# LED_TEST.net
KiCad netlist of a schematic drawn in EAGLE
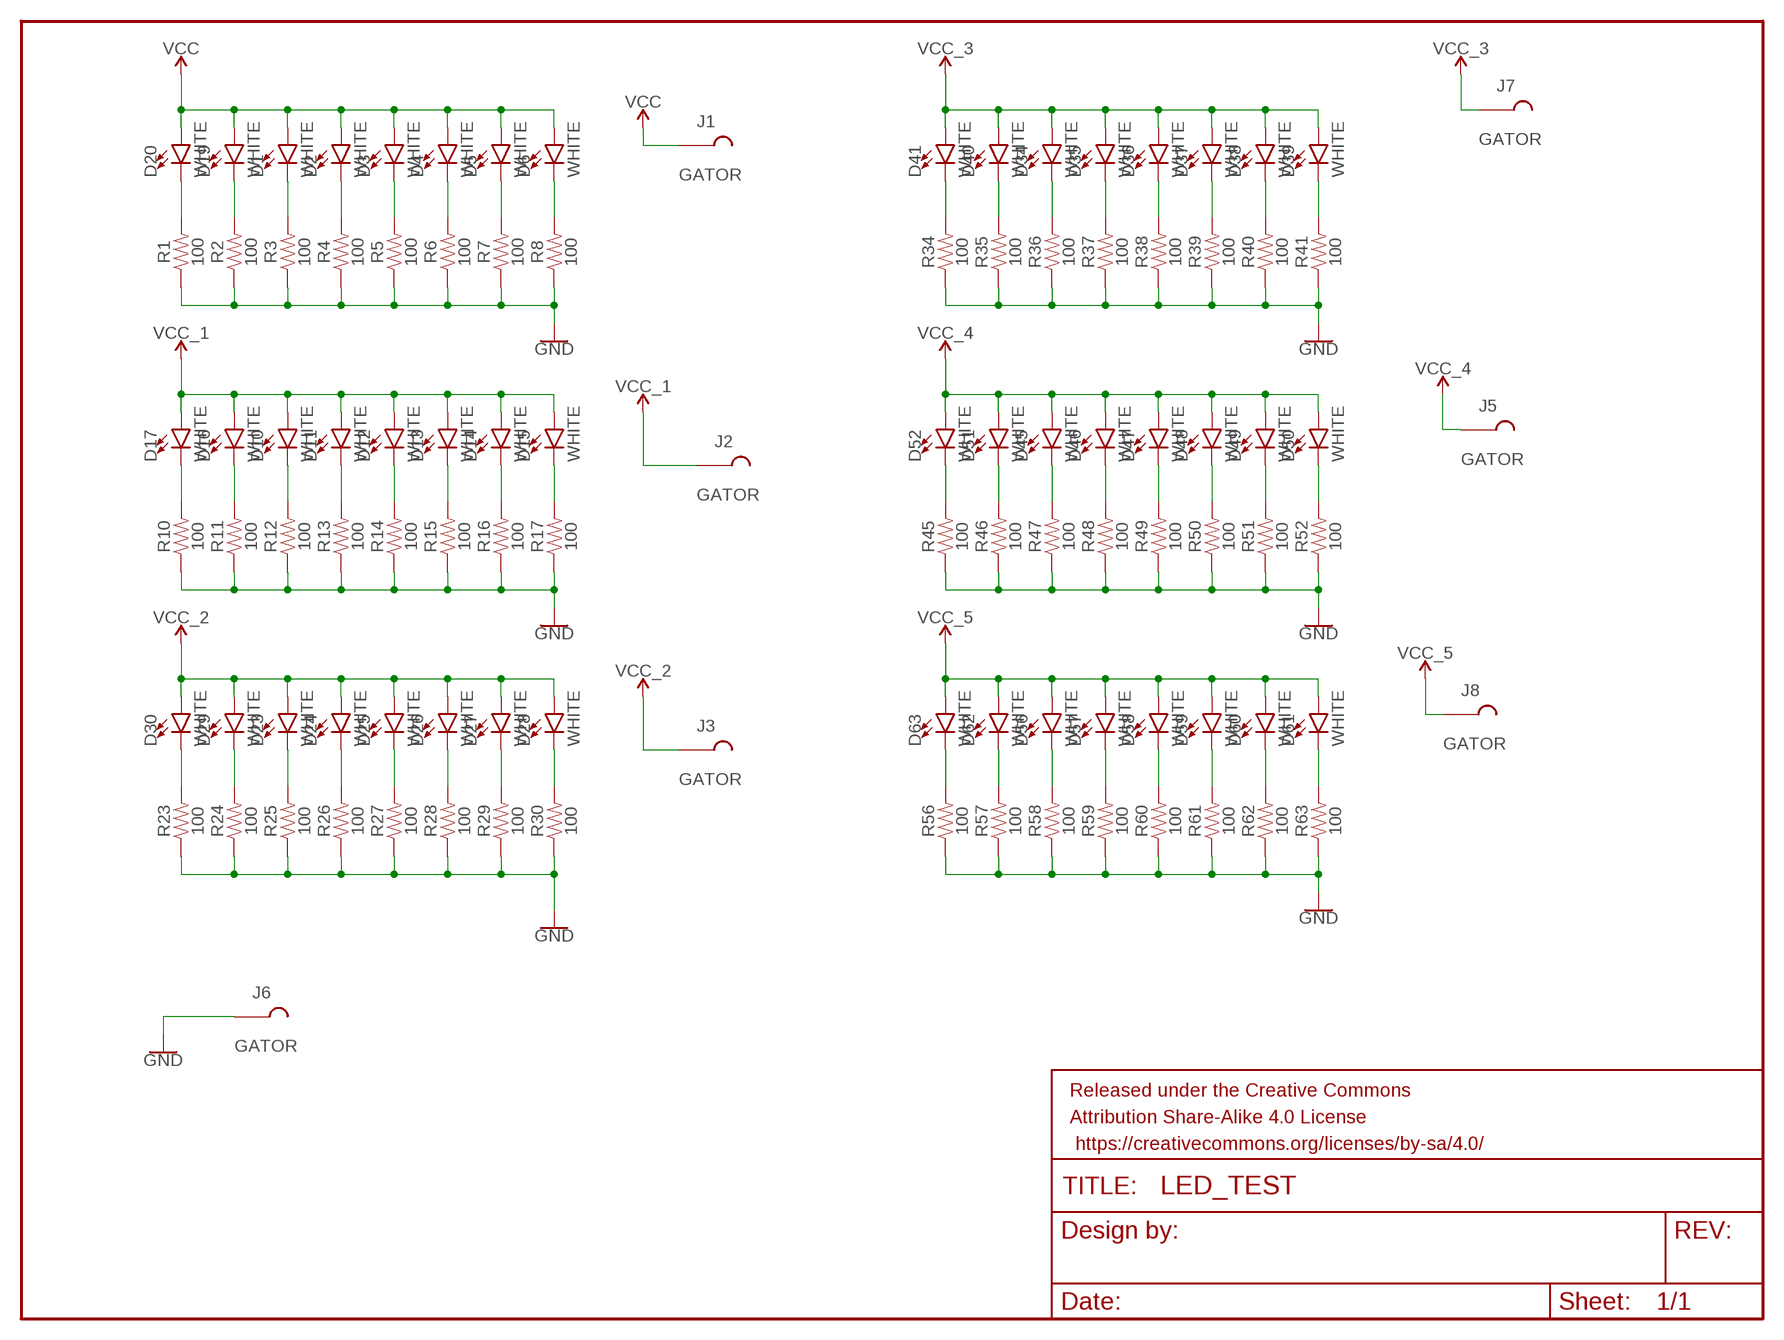
[diagram p0: schematic, sheet 1]

(export (version "E")
  (design (tool "Eeschema 10.0.6"))
  (components
    (comp (ref "D1")
      (value "WHITE")
      (footprint "eagle-import:LED-1206")
      (libsource (lib "eagle-import") (part "LED-WHITE1206"))
    )
    (comp (ref "D2")
      (value "WHITE")
      (footprint "eagle-import:LED-1206")
      (libsource (lib "eagle-import") (part "LED-WHITE1206"))
    )
    (comp (ref "D3")
      (value "WHITE")
      (footprint "eagle-import:LED-1206")
      (libsource (lib "eagle-import") (part "LED-WHITE1206"))
    )
    (comp (ref "D4")
      (value "WHITE")
      (footprint "eagle-import:LED-1206")
      (libsource (lib "eagle-import") (part "LED-WHITE1206"))
    )
    (comp (ref "D5")
      (value "WHITE")
      (footprint "eagle-import:LED-1206")
      (libsource (lib "eagle-import") (part "LED-WHITE1206"))
    )
    (comp (ref "D6")
      (value "WHITE")
      (footprint "eagle-import:LED-1206")
      (libsource (lib "eagle-import") (part "LED-WHITE1206"))
    )
    (comp (ref "D10")
      (value "WHITE")
      (footprint "eagle-import:LED-1206")
      (libsource (lib "eagle-import") (part "LED-WHITE1206"))
    )
    (comp (ref "D11")
      (value "WHITE")
      (footprint "eagle-import:LED-1206")
      (libsource (lib "eagle-import") (part "LED-WHITE1206"))
    )
    (comp (ref "D12")
      (value "WHITE")
      (footprint "eagle-import:LED-1206")
      (libsource (lib "eagle-import") (part "LED-WHITE1206"))
    )
    (comp (ref "D13")
      (value "WHITE")
      (footprint "eagle-import:LED-1206")
      (libsource (lib "eagle-import") (part "LED-WHITE1206"))
    )
    (comp (ref "D14")
      (value "WHITE")
      (footprint "eagle-import:LED-1206")
      (libsource (lib "eagle-import") (part "LED-WHITE1206"))
    )
    (comp (ref "D15")
      (value "WHITE")
      (footprint "eagle-import:LED-1206")
      (libsource (lib "eagle-import") (part "LED-WHITE1206"))
    )
    (comp (ref "D16")
      (value "WHITE")
      (footprint "eagle-import:LED-1206")
      (libsource (lib "eagle-import") (part "LED-WHITE1206"))
    )
    (comp (ref "D17")
      (value "WHITE")
      (footprint "eagle-import:LED-1206")
      (libsource (lib "eagle-import") (part "LED-WHITE1206"))
    )
    (comp (ref "D19")
      (value "WHITE")
      (footprint "eagle-import:LED-1206")
      (libsource (lib "eagle-import") (part "LED-WHITE1206"))
    )
    (comp (ref "D20")
      (value "WHITE")
      (footprint "eagle-import:LED-1206")
      (libsource (lib "eagle-import") (part "LED-WHITE1206"))
    )
    (comp (ref "D23")
      (value "WHITE")
      (footprint "eagle-import:LED-1206")
      (libsource (lib "eagle-import") (part "LED-WHITE1206"))
    )
    (comp (ref "D24")
      (value "WHITE")
      (footprint "eagle-import:LED-1206")
      (libsource (lib "eagle-import") (part "LED-WHITE1206"))
    )
    (comp (ref "D25")
      (value "WHITE")
      (footprint "eagle-import:LED-1206")
      (libsource (lib "eagle-import") (part "LED-WHITE1206"))
    )
    (comp (ref "D26")
      (value "WHITE")
      (footprint "eagle-import:LED-1206")
      (libsource (lib "eagle-import") (part "LED-WHITE1206"))
    )
    (comp (ref "D27")
      (value "WHITE")
      (footprint "eagle-import:LED-1206")
      (libsource (lib "eagle-import") (part "LED-WHITE1206"))
    )
    (comp (ref "D28")
      (value "WHITE")
      (footprint "eagle-import:LED-1206")
      (libsource (lib "eagle-import") (part "LED-WHITE1206"))
    )
    (comp (ref "D29")
      (value "WHITE")
      (footprint "eagle-import:LED-1206")
      (libsource (lib "eagle-import") (part "LED-WHITE1206"))
    )
    (comp (ref "D30")
      (value "WHITE")
      (footprint "eagle-import:LED-1206")
      (libsource (lib "eagle-import") (part "LED-WHITE1206"))
    )
    (comp (ref "D34")
      (value "WHITE")
      (footprint "eagle-import:LED-1206")
      (libsource (lib "eagle-import") (part "LED-WHITE1206"))
    )
    (comp (ref "D35")
      (value "WHITE")
      (footprint "eagle-import:LED-1206")
      (libsource (lib "eagle-import") (part "LED-WHITE1206"))
    )
    (comp (ref "D36")
      (value "WHITE")
      (footprint "eagle-import:LED-1206")
      (libsource (lib "eagle-import") (part "LED-WHITE1206"))
    )
    (comp (ref "D37")
      (value "WHITE")
      (footprint "eagle-import:LED-1206")
      (libsource (lib "eagle-import") (part "LED-WHITE1206"))
    )
    (comp (ref "D38")
      (value "WHITE")
      (footprint "eagle-import:LED-1206")
      (libsource (lib "eagle-import") (part "LED-WHITE1206"))
    )
    (comp (ref "D39")
      (value "WHITE")
      (footprint "eagle-import:LED-1206")
      (libsource (lib "eagle-import") (part "LED-WHITE1206"))
    )
    (comp (ref "D40")
      (value "WHITE")
      (footprint "eagle-import:LED-1206")
      (libsource (lib "eagle-import") (part "LED-WHITE1206"))
    )
    (comp (ref "D41")
      (value "WHITE")
      (footprint "eagle-import:LED-1206")
      (libsource (lib "eagle-import") (part "LED-WHITE1206"))
    )
    (comp (ref "D45")
      (value "WHITE")
      (footprint "eagle-import:LED-1206")
      (libsource (lib "eagle-import") (part "LED-WHITE1206"))
    )
    (comp (ref "D46")
      (value "WHITE")
      (footprint "eagle-import:LED-1206")
      (libsource (lib "eagle-import") (part "LED-WHITE1206"))
    )
    (comp (ref "D47")
      (value "WHITE")
      (footprint "eagle-import:LED-1206")
      (libsource (lib "eagle-import") (part "LED-WHITE1206"))
    )
    (comp (ref "D48")
      (value "WHITE")
      (footprint "eagle-import:LED-1206")
      (libsource (lib "eagle-import") (part "LED-WHITE1206"))
    )
    (comp (ref "D49")
      (value "WHITE")
      (footprint "eagle-import:LED-1206")
      (libsource (lib "eagle-import") (part "LED-WHITE1206"))
    )
    (comp (ref "D50")
      (value "WHITE")
      (footprint "eagle-import:LED-1206")
      (libsource (lib "eagle-import") (part "LED-WHITE1206"))
    )
    (comp (ref "D51")
      (value "WHITE")
      (footprint "eagle-import:LED-1206")
      (libsource (lib "eagle-import") (part "LED-WHITE1206"))
    )
    (comp (ref "D52")
      (value "WHITE")
      (footprint "eagle-import:LED-1206")
      (libsource (lib "eagle-import") (part "LED-WHITE1206"))
    )
    (comp (ref "D56")
      (value "WHITE")
      (footprint "eagle-import:LED-1206")
      (libsource (lib "eagle-import") (part "LED-WHITE1206"))
    )
    (comp (ref "D57")
      (value "WHITE")
      (footprint "eagle-import:LED-1206")
      (libsource (lib "eagle-import") (part "LED-WHITE1206"))
    )
    (comp (ref "D58")
      (value "WHITE")
      (footprint "eagle-import:LED-1206")
      (libsource (lib "eagle-import") (part "LED-WHITE1206"))
    )
    (comp (ref "D59")
      (value "WHITE")
      (footprint "eagle-import:LED-1206")
      (libsource (lib "eagle-import") (part "LED-WHITE1206"))
    )
    (comp (ref "D60")
      (value "WHITE")
      (footprint "eagle-import:LED-1206")
      (libsource (lib "eagle-import") (part "LED-WHITE1206"))
    )
    (comp (ref "D61")
      (value "WHITE")
      (footprint "eagle-import:LED-1206")
      (libsource (lib "eagle-import") (part "LED-WHITE1206"))
    )
    (comp (ref "D62")
      (value "WHITE")
      (footprint "eagle-import:LED-1206")
      (libsource (lib "eagle-import") (part "LED-WHITE1206"))
    )
    (comp (ref "D63")
      (value "WHITE")
      (footprint "eagle-import:LED-1206")
      (libsource (lib "eagle-import") (part "LED-WHITE1206"))
    )
    (comp (ref "FRAME1")
      (value "FRAME-LETTER")
      (footprint "eagle-import:CREATIVE_COMMONS")
      (libsource (lib "eagle-import") (part "FRAME-LETTER"))
    )
    (comp (ref "J1")
      (value "GATOR")
      (footprint "eagle-import:GATOR")
      (libsource (lib "eagle-import") (part "GATOR"))
    )
    (comp (ref "J2")
      (value "GATOR")
      (footprint "eagle-import:GATOR")
      (libsource (lib "eagle-import") (part "GATOR"))
    )
    (comp (ref "J3")
      (value "GATOR")
      (footprint "eagle-import:GATOR")
      (libsource (lib "eagle-import") (part "GATOR"))
    )
    (comp (ref "J5")
      (value "GATOR")
      (footprint "eagle-import:GATOR")
      (libsource (lib "eagle-import") (part "GATOR"))
    )
    (comp (ref "J6")
      (value "GATOR")
      (footprint "eagle-import:GATOR")
      (libsource (lib "eagle-import") (part "GATOR"))
    )
    (comp (ref "J7")
      (value "GATOR")
      (footprint "eagle-import:GATOR")
      (libsource (lib "eagle-import") (part "GATOR"))
    )
    (comp (ref "J8")
      (value "GATOR")
      (footprint "eagle-import:GATOR")
      (libsource (lib "eagle-import") (part "GATOR"))
    )
    (comp (ref "R1")
      (value "100")
      (footprint "eagle-import:0603")
      (libsource (lib "eagle-import") (part "100OHM-0603-1/4W-5%"))
    )
    (comp (ref "R2")
      (value "100")
      (footprint "eagle-import:0603")
      (libsource (lib "eagle-import") (part "100OHM-0603-1/4W-5%"))
    )
    (comp (ref "R3")
      (value "100")
      (footprint "eagle-import:0603")
      (libsource (lib "eagle-import") (part "100OHM-0603-1/4W-5%"))
    )
    (comp (ref "R4")
      (value "100")
      (footprint "eagle-import:0603")
      (libsource (lib "eagle-import") (part "100OHM-0603-1/4W-5%"))
    )
    (comp (ref "R5")
      (value "100")
      (footprint "eagle-import:0603")
      (libsource (lib "eagle-import") (part "100OHM-0603-1/4W-5%"))
    )
    (comp (ref "R6")
      (value "100")
      (footprint "eagle-import:0603")
      (libsource (lib "eagle-import") (part "100OHM-0603-1/4W-5%"))
    )
    (comp (ref "R7")
      (value "100")
      (footprint "eagle-import:0603")
      (libsource (lib "eagle-import") (part "100OHM-0603-1/4W-5%"))
    )
    (comp (ref "R8")
      (value "100")
      (footprint "eagle-import:0603")
      (libsource (lib "eagle-import") (part "100OHM-0603-1/4W-5%"))
    )
    (comp (ref "R10")
      (value "100")
      (footprint "eagle-import:0603")
      (libsource (lib "eagle-import") (part "100OHM-0603-1/4W-5%"))
    )
    (comp (ref "R11")
      (value "100")
      (footprint "eagle-import:0603")
      (libsource (lib "eagle-import") (part "100OHM-0603-1/4W-5%"))
    )
    (comp (ref "R12")
      (value "100")
      (footprint "eagle-import:0603")
      (libsource (lib "eagle-import") (part "100OHM-0603-1/4W-5%"))
    )
    (comp (ref "R13")
      (value "100")
      (footprint "eagle-import:0603")
      (libsource (lib "eagle-import") (part "100OHM-0603-1/4W-5%"))
    )
    (comp (ref "R14")
      (value "100")
      (footprint "eagle-import:0603")
      (libsource (lib "eagle-import") (part "100OHM-0603-1/4W-5%"))
    )
    (comp (ref "R15")
      (value "100")
      (footprint "eagle-import:0603")
      (libsource (lib "eagle-import") (part "100OHM-0603-1/4W-5%"))
    )
    (comp (ref "R16")
      (value "100")
      (footprint "eagle-import:0603")
      (libsource (lib "eagle-import") (part "100OHM-0603-1/4W-5%"))
    )
    (comp (ref "R17")
      (value "100")
      (footprint "eagle-import:0603")
      (libsource (lib "eagle-import") (part "100OHM-0603-1/4W-5%"))
    )
    (comp (ref "R23")
      (value "100")
      (footprint "eagle-import:0603")
      (libsource (lib "eagle-import") (part "100OHM-0603-1/4W-5%"))
    )
    (comp (ref "R24")
      (value "100")
      (footprint "eagle-import:0603")
      (libsource (lib "eagle-import") (part "100OHM-0603-1/4W-5%"))
    )
    (comp (ref "R25")
      (value "100")
      (footprint "eagle-import:0603")
      (libsource (lib "eagle-import") (part "100OHM-0603-1/4W-5%"))
    )
    (comp (ref "R26")
      (value "100")
      (footprint "eagle-import:0603")
      (libsource (lib "eagle-import") (part "100OHM-0603-1/4W-5%"))
    )
    (comp (ref "R27")
      (value "100")
      (footprint "eagle-import:0603")
      (libsource (lib "eagle-import") (part "100OHM-0603-1/4W-5%"))
    )
    (comp (ref "R28")
      (value "100")
      (footprint "eagle-import:0603")
      (libsource (lib "eagle-import") (part "100OHM-0603-1/4W-5%"))
    )
    (comp (ref "R29")
      (value "100")
      (footprint "eagle-import:0603")
      (libsource (lib "eagle-import") (part "100OHM-0603-1/4W-5%"))
    )
    (comp (ref "R30")
      (value "100")
      (footprint "eagle-import:0603")
      (libsource (lib "eagle-import") (part "100OHM-0603-1/4W-5%"))
    )
    (comp (ref "R34")
      (value "100")
      (footprint "eagle-import:0603")
      (libsource (lib "eagle-import") (part "100OHM-0603-1/4W-5%"))
    )
    (comp (ref "R35")
      (value "100")
      (footprint "eagle-import:0603")
      (libsource (lib "eagle-import") (part "100OHM-0603-1/4W-5%"))
    )
    (comp (ref "R36")
      (value "100")
      (footprint "eagle-import:0603")
      (libsource (lib "eagle-import") (part "100OHM-0603-1/4W-5%"))
    )
    (comp (ref "R37")
      (value "100")
      (footprint "eagle-import:0603")
      (libsource (lib "eagle-import") (part "100OHM-0603-1/4W-5%"))
    )
    (comp (ref "R38")
      (value "100")
      (footprint "eagle-import:0603")
      (libsource (lib "eagle-import") (part "100OHM-0603-1/4W-5%"))
    )
    (comp (ref "R39")
      (value "100")
      (footprint "eagle-import:0603")
      (libsource (lib "eagle-import") (part "100OHM-0603-1/4W-5%"))
    )
    (comp (ref "R40")
      (value "100")
      (footprint "eagle-import:0603")
      (libsource (lib "eagle-import") (part "100OHM-0603-1/4W-5%"))
    )
    (comp (ref "R41")
      (value "100")
      (footprint "eagle-import:0603")
      (libsource (lib "eagle-import") (part "100OHM-0603-1/4W-5%"))
    )
    (comp (ref "R45")
      (value "100")
      (footprint "eagle-import:0603")
      (libsource (lib "eagle-import") (part "100OHM-0603-1/4W-5%"))
    )
    (comp (ref "R46")
      (value "100")
      (footprint "eagle-import:0603")
      (libsource (lib "eagle-import") (part "100OHM-0603-1/4W-5%"))
    )
    (comp (ref "R47")
      (value "100")
      (footprint "eagle-import:0603")
      (libsource (lib "eagle-import") (part "100OHM-0603-1/4W-5%"))
    )
    (comp (ref "R48")
      (value "100")
      (footprint "eagle-import:0603")
      (libsource (lib "eagle-import") (part "100OHM-0603-1/4W-5%"))
    )
    (comp (ref "R49")
      (value "100")
      (footprint "eagle-import:0603")
      (libsource (lib "eagle-import") (part "100OHM-0603-1/4W-5%"))
    )
    (comp (ref "R50")
      (value "100")
      (footprint "eagle-import:0603")
      (libsource (lib "eagle-import") (part "100OHM-0603-1/4W-5%"))
    )
    (comp (ref "R51")
      (value "100")
      (footprint "eagle-import:0603")
      (libsource (lib "eagle-import") (part "100OHM-0603-1/4W-5%"))
    )
    (comp (ref "R52")
      (value "100")
      (footprint "eagle-import:0603")
      (libsource (lib "eagle-import") (part "100OHM-0603-1/4W-5%"))
    )
    (comp (ref "R56")
      (value "100")
      (footprint "eagle-import:0603")
      (libsource (lib "eagle-import") (part "100OHM-0603-1/4W-5%"))
    )
    (comp (ref "R57")
      (value "100")
      (footprint "eagle-import:0603")
      (libsource (lib "eagle-import") (part "100OHM-0603-1/4W-5%"))
    )
    (comp (ref "R58")
      (value "100")
      (footprint "eagle-import:0603")
      (libsource (lib "eagle-import") (part "100OHM-0603-1/4W-5%"))
    )
    (comp (ref "R59")
      (value "100")
      (footprint "eagle-import:0603")
      (libsource (lib "eagle-import") (part "100OHM-0603-1/4W-5%"))
    )
    (comp (ref "R60")
      (value "100")
      (footprint "eagle-import:0603")
      (libsource (lib "eagle-import") (part "100OHM-0603-1/4W-5%"))
    )
    (comp (ref "R61")
      (value "100")
      (footprint "eagle-import:0603")
      (libsource (lib "eagle-import") (part "100OHM-0603-1/4W-5%"))
    )
    (comp (ref "R62")
      (value "100")
      (footprint "eagle-import:0603")
      (libsource (lib "eagle-import") (part "100OHM-0603-1/4W-5%"))
    )
    (comp (ref "R63")
      (value "100")
      (footprint "eagle-import:0603")
      (libsource (lib "eagle-import") (part "100OHM-0603-1/4W-5%"))
    )
  )
  (nets
    (net (code "1") (name "GND") (class "Default")
      (node (ref "J6") (pin "P$1") (pinfunction "P$1_P$1") (pintype "bidirectional"))
      (node (ref "J6") (pin "P$2") (pinfunction "P$1_P$2") (pintype "bidirectional"))
      (node (ref "R1") (pin "1") (pinfunction "1_1") (pintype "passive"))
      (node (ref "R10") (pin "1") (pinfunction "1_1") (pintype "passive"))
      (node (ref "R11") (pin "1") (pinfunction "1_1") (pintype "passive"))
      (node (ref "R12") (pin "1") (pinfunction "1_1") (pintype "passive"))
      (node (ref "R13") (pin "1") (pinfunction "1_1") (pintype "passive"))
      (node (ref "R14") (pin "1") (pinfunction "1_1") (pintype "passive"))
      (node (ref "R15") (pin "1") (pinfunction "1_1") (pintype "passive"))
      (node (ref "R16") (pin "1") (pinfunction "1_1") (pintype "passive"))
      (node (ref "R17") (pin "1") (pinfunction "1_1") (pintype "passive"))
      (node (ref "R2") (pin "1") (pinfunction "1_1") (pintype "passive"))
      (node (ref "R23") (pin "1") (pinfunction "1_1") (pintype "passive"))
      (node (ref "R24") (pin "1") (pinfunction "1_1") (pintype "passive"))
      (node (ref "R25") (pin "1") (pinfunction "1_1") (pintype "passive"))
      (node (ref "R26") (pin "1") (pinfunction "1_1") (pintype "passive"))
      (node (ref "R27") (pin "1") (pinfunction "1_1") (pintype "passive"))
      (node (ref "R28") (pin "1") (pinfunction "1_1") (pintype "passive"))
      (node (ref "R29") (pin "1") (pinfunction "1_1") (pintype "passive"))
      (node (ref "R3") (pin "1") (pinfunction "1_1") (pintype "passive"))
      (node (ref "R30") (pin "1") (pinfunction "1_1") (pintype "passive"))
      (node (ref "R34") (pin "1") (pinfunction "1_1") (pintype "passive"))
      (node (ref "R35") (pin "1") (pinfunction "1_1") (pintype "passive"))
      (node (ref "R36") (pin "1") (pinfunction "1_1") (pintype "passive"))
      (node (ref "R37") (pin "1") (pinfunction "1_1") (pintype "passive"))
      (node (ref "R38") (pin "1") (pinfunction "1_1") (pintype "passive"))
      (node (ref "R39") (pin "1") (pinfunction "1_1") (pintype "passive"))
      (node (ref "R4") (pin "1") (pinfunction "1_1") (pintype "passive"))
      (node (ref "R40") (pin "1") (pinfunction "1_1") (pintype "passive"))
      (node (ref "R41") (pin "1") (pinfunction "1_1") (pintype "passive"))
      (node (ref "R45") (pin "1") (pinfunction "1_1") (pintype "passive"))
      (node (ref "R46") (pin "1") (pinfunction "1_1") (pintype "passive"))
      (node (ref "R47") (pin "1") (pinfunction "1_1") (pintype "passive"))
      (node (ref "R48") (pin "1") (pinfunction "1_1") (pintype "passive"))
      (node (ref "R49") (pin "1") (pinfunction "1_1") (pintype "passive"))
      (node (ref "R5") (pin "1") (pinfunction "1_1") (pintype "passive"))
      (node (ref "R50") (pin "1") (pinfunction "1_1") (pintype "passive"))
      (node (ref "R51") (pin "1") (pinfunction "1_1") (pintype "passive"))
      (node (ref "R52") (pin "1") (pinfunction "1_1") (pintype "passive"))
      (node (ref "R56") (pin "1") (pinfunction "1_1") (pintype "passive"))
      (node (ref "R57") (pin "1") (pinfunction "1_1") (pintype "passive"))
      (node (ref "R58") (pin "1") (pinfunction "1_1") (pintype "passive"))
      (node (ref "R59") (pin "1") (pinfunction "1_1") (pintype "passive"))
      (node (ref "R6") (pin "1") (pinfunction "1_1") (pintype "passive"))
      (node (ref "R60") (pin "1") (pinfunction "1_1") (pintype "passive"))
      (node (ref "R61") (pin "1") (pinfunction "1_1") (pintype "passive"))
      (node (ref "R62") (pin "1") (pinfunction "1_1") (pintype "passive"))
      (node (ref "R63") (pin "1") (pinfunction "1_1") (pintype "passive"))
      (node (ref "R7") (pin "1") (pinfunction "1_1") (pintype "passive"))
      (node (ref "R8") (pin "1") (pinfunction "1_1") (pintype "passive"))
    )
    (net (code "2") (name "Net-(D1-PadC)") (class "Default")
      (node (ref "D1") (pin "C") (pinfunction "C_C") (pintype "passive"))
      (node (ref "R3") (pin "2") (pinfunction "2_2") (pintype "passive"))
    )
    (net (code "3") (name "Net-(D2-PadC)") (class "Default")
      (node (ref "D2") (pin "C") (pinfunction "C_C") (pintype "passive"))
      (node (ref "R4") (pin "2") (pinfunction "2_2") (pintype "passive"))
    )
    (net (code "4") (name "Net-(D3-PadC)") (class "Default")
      (node (ref "D3") (pin "C") (pinfunction "C_C") (pintype "passive"))
      (node (ref "R5") (pin "2") (pinfunction "2_2") (pintype "passive"))
    )
    (net (code "5") (name "Net-(D4-PadC)") (class "Default")
      (node (ref "D4") (pin "C") (pinfunction "C_C") (pintype "passive"))
      (node (ref "R6") (pin "2") (pinfunction "2_2") (pintype "passive"))
    )
    (net (code "6") (name "Net-(D5-PadC)") (class "Default")
      (node (ref "D5") (pin "C") (pinfunction "C_C") (pintype "passive"))
      (node (ref "R7") (pin "2") (pinfunction "2_2") (pintype "passive"))
    )
    (net (code "7") (name "Net-(D6-PadC)") (class "Default")
      (node (ref "D6") (pin "C") (pinfunction "C_C") (pintype "passive"))
      (node (ref "R8") (pin "2") (pinfunction "2_2") (pintype "passive"))
    )
    (net (code "8") (name "Net-(D10-PadC)") (class "Default")
      (node (ref "D10") (pin "C") (pinfunction "C_C") (pintype "passive"))
      (node (ref "R12") (pin "2") (pinfunction "2_2") (pintype "passive"))
    )
    (net (code "9") (name "Net-(D11-PadC)") (class "Default")
      (node (ref "D11") (pin "C") (pinfunction "C_C") (pintype "passive"))
      (node (ref "R13") (pin "2") (pinfunction "2_2") (pintype "passive"))
    )
    (net (code "10") (name "Net-(D12-PadC)") (class "Default")
      (node (ref "D12") (pin "C") (pinfunction "C_C") (pintype "passive"))
      (node (ref "R14") (pin "2") (pinfunction "2_2") (pintype "passive"))
    )
    (net (code "11") (name "Net-(D13-PadC)") (class "Default")
      (node (ref "D13") (pin "C") (pinfunction "C_C") (pintype "passive"))
      (node (ref "R15") (pin "2") (pinfunction "2_2") (pintype "passive"))
    )
    (net (code "12") (name "Net-(D14-PadC)") (class "Default")
      (node (ref "D14") (pin "C") (pinfunction "C_C") (pintype "passive"))
      (node (ref "R16") (pin "2") (pinfunction "2_2") (pintype "passive"))
    )
    (net (code "13") (name "Net-(D15-PadC)") (class "Default")
      (node (ref "D15") (pin "C") (pinfunction "C_C") (pintype "passive"))
      (node (ref "R17") (pin "2") (pinfunction "2_2") (pintype "passive"))
    )
    (net (code "14") (name "Net-(D16-PadC)") (class "Default")
      (node (ref "D16") (pin "C") (pinfunction "C_C") (pintype "passive"))
      (node (ref "R11") (pin "2") (pinfunction "2_2") (pintype "passive"))
    )
    (net (code "15") (name "Net-(D17-PadC)") (class "Default")
      (node (ref "D17") (pin "C") (pinfunction "C_C") (pintype "passive"))
      (node (ref "R10") (pin "2") (pinfunction "2_2") (pintype "passive"))
    )
    (net (code "16") (name "Net-(D19-PadC)") (class "Default")
      (node (ref "D19") (pin "C") (pinfunction "C_C") (pintype "passive"))
      (node (ref "R2") (pin "2") (pinfunction "2_2") (pintype "passive"))
    )
    (net (code "17") (name "Net-(D20-PadC)") (class "Default")
      (node (ref "D20") (pin "C") (pinfunction "C_C") (pintype "passive"))
      (node (ref "R1") (pin "2") (pinfunction "2_2") (pintype "passive"))
    )
    (net (code "18") (name "Net-(D23-PadC)") (class "Default")
      (node (ref "D23") (pin "C") (pinfunction "C_C") (pintype "passive"))
      (node (ref "R25") (pin "2") (pinfunction "2_2") (pintype "passive"))
    )
    (net (code "19") (name "Net-(D24-PadC)") (class "Default")
      (node (ref "D24") (pin "C") (pinfunction "C_C") (pintype "passive"))
      (node (ref "R26") (pin "2") (pinfunction "2_2") (pintype "passive"))
    )
    (net (code "20") (name "Net-(D25-PadC)") (class "Default")
      (node (ref "D25") (pin "C") (pinfunction "C_C") (pintype "passive"))
      (node (ref "R27") (pin "2") (pinfunction "2_2") (pintype "passive"))
    )
    (net (code "21") (name "Net-(D26-PadC)") (class "Default")
      (node (ref "D26") (pin "C") (pinfunction "C_C") (pintype "passive"))
      (node (ref "R28") (pin "2") (pinfunction "2_2") (pintype "passive"))
    )
    (net (code "22") (name "Net-(D27-PadC)") (class "Default")
      (node (ref "D27") (pin "C") (pinfunction "C_C") (pintype "passive"))
      (node (ref "R29") (pin "2") (pinfunction "2_2") (pintype "passive"))
    )
    (net (code "23") (name "Net-(D28-PadC)") (class "Default")
      (node (ref "D28") (pin "C") (pinfunction "C_C") (pintype "passive"))
      (node (ref "R30") (pin "2") (pinfunction "2_2") (pintype "passive"))
    )
    (net (code "24") (name "Net-(D29-PadC)") (class "Default")
      (node (ref "D29") (pin "C") (pinfunction "C_C") (pintype "passive"))
      (node (ref "R24") (pin "2") (pinfunction "2_2") (pintype "passive"))
    )
    (net (code "25") (name "Net-(D30-PadC)") (class "Default")
      (node (ref "D30") (pin "C") (pinfunction "C_C") (pintype "passive"))
      (node (ref "R23") (pin "2") (pinfunction "2_2") (pintype "passive"))
    )
    (net (code "26") (name "Net-(D34-PadC)") (class "Default")
      (node (ref "D34") (pin "C") (pinfunction "C_C") (pintype "passive"))
      (node (ref "R36") (pin "2") (pinfunction "2_2") (pintype "passive"))
    )
    (net (code "27") (name "Net-(D35-PadC)") (class "Default")
      (node (ref "D35") (pin "C") (pinfunction "C_C") (pintype "passive"))
      (node (ref "R37") (pin "2") (pinfunction "2_2") (pintype "passive"))
    )
    (net (code "28") (name "Net-(D36-PadC)") (class "Default")
      (node (ref "D36") (pin "C") (pinfunction "C_C") (pintype "passive"))
      (node (ref "R38") (pin "2") (pinfunction "2_2") (pintype "passive"))
    )
    (net (code "29") (name "Net-(D37-PadC)") (class "Default")
      (node (ref "D37") (pin "C") (pinfunction "C_C") (pintype "passive"))
      (node (ref "R39") (pin "2") (pinfunction "2_2") (pintype "passive"))
    )
    (net (code "30") (name "Net-(D38-PadC)") (class "Default")
      (node (ref "D38") (pin "C") (pinfunction "C_C") (pintype "passive"))
      (node (ref "R40") (pin "2") (pinfunction "2_2") (pintype "passive"))
    )
    (net (code "31") (name "Net-(D39-PadC)") (class "Default")
      (node (ref "D39") (pin "C") (pinfunction "C_C") (pintype "passive"))
      (node (ref "R41") (pin "2") (pinfunction "2_2") (pintype "passive"))
    )
    (net (code "32") (name "Net-(D40-PadC)") (class "Default")
      (node (ref "D40") (pin "C") (pinfunction "C_C") (pintype "passive"))
      (node (ref "R35") (pin "2") (pinfunction "2_2") (pintype "passive"))
    )
    (net (code "33") (name "Net-(D41-PadC)") (class "Default")
      (node (ref "D41") (pin "C") (pinfunction "C_C") (pintype "passive"))
      (node (ref "R34") (pin "2") (pinfunction "2_2") (pintype "passive"))
    )
    (net (code "34") (name "Net-(D45-PadC)") (class "Default")
      (node (ref "D45") (pin "C") (pinfunction "C_C") (pintype "passive"))
      (node (ref "R47") (pin "2") (pinfunction "2_2") (pintype "passive"))
    )
    (net (code "35") (name "Net-(D46-PadC)") (class "Default")
      (node (ref "D46") (pin "C") (pinfunction "C_C") (pintype "passive"))
      (node (ref "R48") (pin "2") (pinfunction "2_2") (pintype "passive"))
    )
    (net (code "36") (name "Net-(D47-PadC)") (class "Default")
      (node (ref "D47") (pin "C") (pinfunction "C_C") (pintype "passive"))
      (node (ref "R49") (pin "2") (pinfunction "2_2") (pintype "passive"))
    )
    (net (code "37") (name "Net-(D48-PadC)") (class "Default")
      (node (ref "D48") (pin "C") (pinfunction "C_C") (pintype "passive"))
      (node (ref "R50") (pin "2") (pinfunction "2_2") (pintype "passive"))
    )
    (net (code "38") (name "Net-(D49-PadC)") (class "Default")
      (node (ref "D49") (pin "C") (pinfunction "C_C") (pintype "passive"))
      (node (ref "R51") (pin "2") (pinfunction "2_2") (pintype "passive"))
    )
    (net (code "39") (name "Net-(D50-PadC)") (class "Default")
      (node (ref "D50") (pin "C") (pinfunction "C_C") (pintype "passive"))
      (node (ref "R52") (pin "2") (pinfunction "2_2") (pintype "passive"))
    )
    (net (code "40") (name "Net-(D51-PadC)") (class "Default")
      (node (ref "D51") (pin "C") (pinfunction "C_C") (pintype "passive"))
      (node (ref "R46") (pin "2") (pinfunction "2_2") (pintype "passive"))
    )
    (net (code "41") (name "Net-(D52-PadC)") (class "Default")
      (node (ref "D52") (pin "C") (pinfunction "C_C") (pintype "passive"))
      (node (ref "R45") (pin "2") (pinfunction "2_2") (pintype "passive"))
    )
    (net (code "42") (name "Net-(D56-PadC)") (class "Default")
      (node (ref "D56") (pin "C") (pinfunction "C_C") (pintype "passive"))
      (node (ref "R58") (pin "2") (pinfunction "2_2") (pintype "passive"))
    )
    (net (code "43") (name "Net-(D57-PadC)") (class "Default")
      (node (ref "D57") (pin "C") (pinfunction "C_C") (pintype "passive"))
      (node (ref "R59") (pin "2") (pinfunction "2_2") (pintype "passive"))
    )
    (net (code "44") (name "Net-(D58-PadC)") (class "Default")
      (node (ref "D58") (pin "C") (pinfunction "C_C") (pintype "passive"))
      (node (ref "R60") (pin "2") (pinfunction "2_2") (pintype "passive"))
    )
    (net (code "45") (name "Net-(D59-PadC)") (class "Default")
      (node (ref "D59") (pin "C") (pinfunction "C_C") (pintype "passive"))
      (node (ref "R61") (pin "2") (pinfunction "2_2") (pintype "passive"))
    )
    (net (code "46") (name "Net-(D60-PadC)") (class "Default")
      (node (ref "D60") (pin "C") (pinfunction "C_C") (pintype "passive"))
      (node (ref "R62") (pin "2") (pinfunction "2_2") (pintype "passive"))
    )
    (net (code "47") (name "Net-(D61-PadC)") (class "Default")
      (node (ref "D61") (pin "C") (pinfunction "C_C") (pintype "passive"))
      (node (ref "R63") (pin "2") (pinfunction "2_2") (pintype "passive"))
    )
    (net (code "48") (name "Net-(D62-PadC)") (class "Default")
      (node (ref "D62") (pin "C") (pinfunction "C_C") (pintype "passive"))
      (node (ref "R57") (pin "2") (pinfunction "2_2") (pintype "passive"))
    )
    (net (code "49") (name "Net-(D63-PadC)") (class "Default")
      (node (ref "D63") (pin "C") (pinfunction "C_C") (pintype "passive"))
      (node (ref "R56") (pin "2") (pinfunction "2_2") (pintype "passive"))
    )
    (net (code "50") (name "VCC") (class "Default")
      (node (ref "D1") (pin "A") (pinfunction "A_A") (pintype "passive"))
      (node (ref "D19") (pin "A") (pinfunction "A_A") (pintype "passive"))
      (node (ref "D2") (pin "A") (pinfunction "A_A") (pintype "passive"))
      (node (ref "D20") (pin "A") (pinfunction "A_A") (pintype "passive"))
      (node (ref "D3") (pin "A") (pinfunction "A_A") (pintype "passive"))
      (node (ref "D4") (pin "A") (pinfunction "A_A") (pintype "passive"))
      (node (ref "D5") (pin "A") (pinfunction "A_A") (pintype "passive"))
      (node (ref "D6") (pin "A") (pinfunction "A_A") (pintype "passive"))
      (node (ref "J1") (pin "P$1") (pinfunction "P$1_P$1") (pintype "bidirectional"))
      (node (ref "J1") (pin "P$2") (pinfunction "P$1_P$2") (pintype "bidirectional"))
    )
    (net (code "51") (name "VCC_1") (class "Default")
      (node (ref "D10") (pin "A") (pinfunction "A_A") (pintype "passive"))
      (node (ref "D11") (pin "A") (pinfunction "A_A") (pintype "passive"))
      (node (ref "D12") (pin "A") (pinfunction "A_A") (pintype "passive"))
      (node (ref "D13") (pin "A") (pinfunction "A_A") (pintype "passive"))
      (node (ref "D14") (pin "A") (pinfunction "A_A") (pintype "passive"))
      (node (ref "D15") (pin "A") (pinfunction "A_A") (pintype "passive"))
      (node (ref "D16") (pin "A") (pinfunction "A_A") (pintype "passive"))
      (node (ref "D17") (pin "A") (pinfunction "A_A") (pintype "passive"))
      (node (ref "J2") (pin "P$1") (pinfunction "P$1_P$1") (pintype "bidirectional"))
      (node (ref "J2") (pin "P$2") (pinfunction "P$1_P$2") (pintype "bidirectional"))
    )
    (net (code "52") (name "VCC_2") (class "Default")
      (node (ref "D23") (pin "A") (pinfunction "A_A") (pintype "passive"))
      (node (ref "D24") (pin "A") (pinfunction "A_A") (pintype "passive"))
      (node (ref "D25") (pin "A") (pinfunction "A_A") (pintype "passive"))
      (node (ref "D26") (pin "A") (pinfunction "A_A") (pintype "passive"))
      (node (ref "D27") (pin "A") (pinfunction "A_A") (pintype "passive"))
      (node (ref "D28") (pin "A") (pinfunction "A_A") (pintype "passive"))
      (node (ref "D29") (pin "A") (pinfunction "A_A") (pintype "passive"))
      (node (ref "D30") (pin "A") (pinfunction "A_A") (pintype "passive"))
      (node (ref "J3") (pin "P$1") (pinfunction "P$1_P$1") (pintype "bidirectional"))
      (node (ref "J3") (pin "P$2") (pinfunction "P$1_P$2") (pintype "bidirectional"))
    )
    (net (code "53") (name "VCC_3") (class "Default")
      (node (ref "D34") (pin "A") (pinfunction "A_A") (pintype "passive"))
      (node (ref "D35") (pin "A") (pinfunction "A_A") (pintype "passive"))
      (node (ref "D36") (pin "A") (pinfunction "A_A") (pintype "passive"))
      (node (ref "D37") (pin "A") (pinfunction "A_A") (pintype "passive"))
      (node (ref "D38") (pin "A") (pinfunction "A_A") (pintype "passive"))
      (node (ref "D39") (pin "A") (pinfunction "A_A") (pintype "passive"))
      (node (ref "D40") (pin "A") (pinfunction "A_A") (pintype "passive"))
      (node (ref "D41") (pin "A") (pinfunction "A_A") (pintype "passive"))
      (node (ref "J7") (pin "P$1") (pinfunction "P$1_P$1") (pintype "bidirectional"))
      (node (ref "J7") (pin "P$2") (pinfunction "P$1_P$2") (pintype "bidirectional"))
    )
    (net (code "54") (name "VCC_4") (class "Default")
      (node (ref "D45") (pin "A") (pinfunction "A_A") (pintype "passive"))
      (node (ref "D46") (pin "A") (pinfunction "A_A") (pintype "passive"))
      (node (ref "D47") (pin "A") (pinfunction "A_A") (pintype "passive"))
      (node (ref "D48") (pin "A") (pinfunction "A_A") (pintype "passive"))
      (node (ref "D49") (pin "A") (pinfunction "A_A") (pintype "passive"))
      (node (ref "D50") (pin "A") (pinfunction "A_A") (pintype "passive"))
      (node (ref "D51") (pin "A") (pinfunction "A_A") (pintype "passive"))
      (node (ref "D52") (pin "A") (pinfunction "A_A") (pintype "passive"))
      (node (ref "J5") (pin "P$1") (pinfunction "P$1_P$1") (pintype "bidirectional"))
      (node (ref "J5") (pin "P$2") (pinfunction "P$1_P$2") (pintype "bidirectional"))
    )
    (net (code "55") (name "VCC_5") (class "Default")
      (node (ref "D56") (pin "A") (pinfunction "A_A") (pintype "passive"))
      (node (ref "D57") (pin "A") (pinfunction "A_A") (pintype "passive"))
      (node (ref "D58") (pin "A") (pinfunction "A_A") (pintype "passive"))
      (node (ref "D59") (pin "A") (pinfunction "A_A") (pintype "passive"))
      (node (ref "D60") (pin "A") (pinfunction "A_A") (pintype "passive"))
      (node (ref "D61") (pin "A") (pinfunction "A_A") (pintype "passive"))
      (node (ref "D62") (pin "A") (pinfunction "A_A") (pintype "passive"))
      (node (ref "D63") (pin "A") (pinfunction "A_A") (pintype "passive"))
      (node (ref "J8") (pin "P$1") (pinfunction "P$1_P$1") (pintype "bidirectional"))
      (node (ref "J8") (pin "P$2") (pinfunction "P$1_P$2") (pintype "bidirectional"))
    )
  )
)
